# ESP8266_MySensorsGateway_v1_4_1.net
KiCad netlist of a schematic drawn in EAGLE
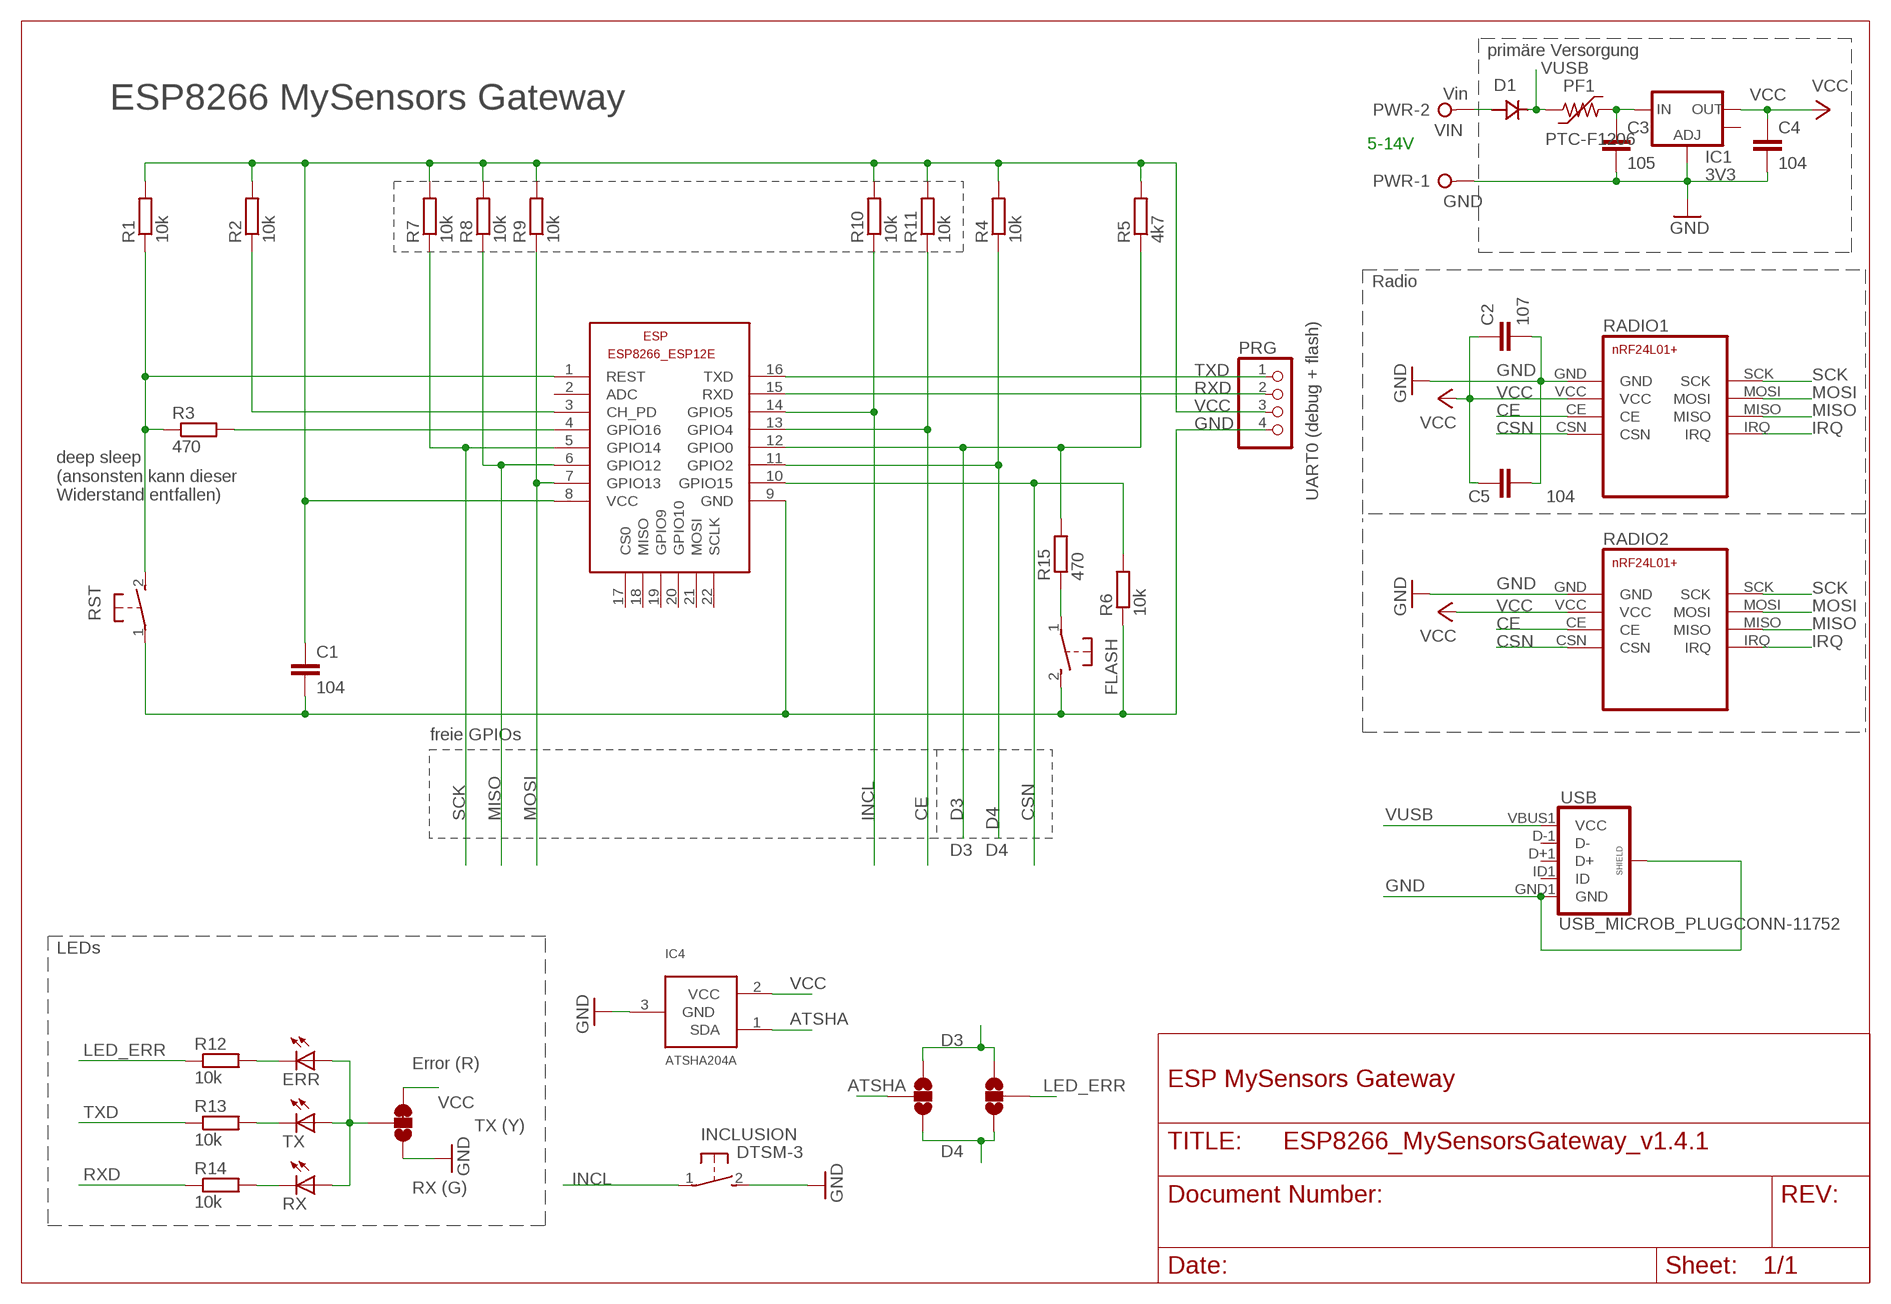
[diagram p0: schematic, sheet 1]

(export (version "E")
  (design (tool "Eeschema 10.0.6"))
  (components
    (comp (ref "C1")
      (value "104")
      (footprint "eagle-import:C0805")
      (libsource (lib "eagle-import") (part "C-EUC0805"))
    )
    (comp (ref "C2")
      (value "107")
      (footprint "eagle-import:MY1210")
      (libsource (lib "eagle-import") (part "C"))
    )
    (comp (ref "C3")
      (value "105")
      (footprint "eagle-import:C0805")
      (libsource (lib "eagle-import") (part "C-EUC0805"))
    )
    (comp (ref "C4")
      (value "104")
      (footprint "eagle-import:C0805")
      (libsource (lib "eagle-import") (part "C-EUC0805"))
    )
    (comp (ref "C5")
      (value "104")
      (footprint "eagle-import:C0805")
      (libsource (lib "eagle-import") (part "C-EUC0805"))
    )
    (comp (ref "D1")
      (value "SS14")
      (footprint "eagle-import:DO214")
      (libsource (lib "eagle-import") (part "SS14"))
    )
    (comp (ref "ERR")
      (value "R")
      (footprint "eagle-import:CHIPLED_1206")
      (libsource (lib "eagle-import") (part "LEDCHIPLED_1206"))
    )
    (comp (ref "ESP")
      (value "µC")
      (footprint "eagle-import:ESP8266-ESP12E")
      (libsource (lib "eagle-import") (part "ESP8266-12EESP8266-ESP12E"))
    )
    (comp (ref "FLASH")
      (value "DTSM-3")
      (footprint "eagle-import:DTSM-3")
      (libsource (lib "eagle-import") (part "DTSM-3"))
    )
    (comp (ref "IC1")
      (value "3V3")
      (footprint "eagle-import:SOT223")
      (libsource (lib "eagle-import") (part "V_REG_LM1117SOT223"))
    )
    (comp (ref "IC4")
      (value "ATSHA204A")
      (footprint "eagle-import:SOT23")
      (libsource (lib "eagle-import") (part "ATSHA204A"))
    )
    (comp (ref "INCLUSION")
      (value "DTSM-3")
      (footprint "eagle-import:DTSM-3")
      (libsource (lib "eagle-import") (part "DTSM-3"))
    )
    (comp (ref "PF1")
      (value "PTC-F1206")
      (footprint "eagle-import:F1206")
      (libsource (lib "eagle-import") (part "PTC-F1206"))
    )
    (comp (ref "PRG")
      (value "PINHD-1X4_S")
      (footprint "eagle-import:1X04")
      (libsource (lib "eagle-import") (part "PINHD-1X4_S"))
    )
    (comp (ref "PWR")
      (value "Vin")
      (footprint "eagle-import:W237-132")
      (libsource (lib "eagle-import") (part "W237-02P"))
    )
    (comp (ref "R1")
      (value "10k")
      (footprint "eagle-import:R0805")
      (libsource (lib "eagle-import") (part "resistor_R-EU_R0805"))
    )
    (comp (ref "R2")
      (value "10k")
      (footprint "eagle-import:R0805")
      (libsource (lib "eagle-import") (part "resistor_R-EU_R0805"))
    )
    (comp (ref "R3")
      (value "470")
      (footprint "eagle-import:R0805")
      (libsource (lib "eagle-import") (part "resistor_R-EU_R0805"))
    )
    (comp (ref "R4")
      (value "10k")
      (footprint "eagle-import:R0805")
      (libsource (lib "eagle-import") (part "resistor_R-EU_R0805"))
    )
    (comp (ref "R5")
      (value "4k7")
      (footprint "eagle-import:R0805")
      (libsource (lib "eagle-import") (part "resistor_R-EU_R0805"))
    )
    (comp (ref "R6")
      (value "10k")
      (footprint "eagle-import:R0805")
      (libsource (lib "eagle-import") (part "resistor_R-EU_R0805"))
    )
    (comp (ref "R7")
      (value "10k")
      (footprint "eagle-import:R0805")
      (libsource (lib "eagle-import") (part "resistor_R-EU_R0805"))
    )
    (comp (ref "R8")
      (value "10k")
      (footprint "eagle-import:R0805")
      (libsource (lib "eagle-import") (part "resistor_R-EU_R0805"))
    )
    (comp (ref "R9")
      (value "10k")
      (footprint "eagle-import:R0805")
      (libsource (lib "eagle-import") (part "resistor_R-EU_R0805"))
    )
    (comp (ref "R10")
      (value "10k")
      (footprint "eagle-import:R0805")
      (libsource (lib "eagle-import") (part "resistor_R-EU_R0805"))
    )
    (comp (ref "R11")
      (value "10k")
      (footprint "eagle-import:R0805")
      (libsource (lib "eagle-import") (part "resistor_R-EU_R0805"))
    )
    (comp (ref "R12")
      (value "10k")
      (footprint "eagle-import:R0805")
      (libsource (lib "eagle-import") (part "R-EU_R0805"))
    )
    (comp (ref "R13")
      (value "10k")
      (footprint "eagle-import:R0805")
      (libsource (lib "eagle-import") (part "R-EU_R0805"))
    )
    (comp (ref "R14")
      (value "10k")
      (footprint "eagle-import:R0805")
      (libsource (lib "eagle-import") (part "R-EU_R0805"))
    )
    (comp (ref "R15")
      (value "470")
      (footprint "eagle-import:R0805")
      (libsource (lib "eagle-import") (part "resistor_R-EU_R0805"))
    )
    (comp (ref "RADIO1")
      (value "NRF24L01+")
      (footprint "eagle-import:NRF24L01+")
      (libsource (lib "eagle-import") (part "NRF24L01+"))
    )
    (comp (ref "RADIO2")
      (value "NRF24L01+NRF24L01+MINI")
      (footprint "eagle-import:NRF24L01+MINI")
      (libsource (lib "eagle-import") (part "NRF24L01+NRF24L01+MINI"))
    )
    (comp (ref "RST")
      (value "DTSM-3")
      (footprint "eagle-import:DTSM-3")
      (libsource (lib "eagle-import") (part "DTSM-3"))
    )
    (comp (ref "RX")
      (value "G")
      (footprint "eagle-import:CHIPLED_1206")
      (libsource (lib "eagle-import") (part "LEDCHIPLED_1206"))
    )
    (comp (ref "SJ1")
      (value "JUMPER-PAD-3-2OF3_NC_BY_TRACE_SMALL")
      (footprint "eagle-import:PAD-JUMPER-3-2OF3_NC_BY_TRACE_YES_SILK_FULL_BOX")
      (libsource (lib "eagle-import") (part "JUMPER-PAD-3-2OF3_NC_BY_TRACE_SMALL"))
    )
    (comp (ref "SJ2")
      (value "JUMPER-PAD-3-NOYES_SILK")
      (footprint "eagle-import:PAD-JUMPER-3-NO_YES_SILK")
      (libsource (lib "eagle-import") (part "JUMPER-PAD-3-NOYES_SILK"))
    )
    (comp (ref "SJ3")
      (value "JUMPER-PAD-3-NOYES_SILK")
      (footprint "eagle-import:PAD-JUMPER-3-NO_YES_SILK")
      (libsource (lib "eagle-import") (part "JUMPER-PAD-3-NOYES_SILK"))
    )
    (comp (ref "TX")
      (value "Y")
      (footprint "eagle-import:CHIPLED_1206")
      (libsource (lib "eagle-import") (part "LEDCHIPLED_1206"))
    )
    (comp (ref "USB")
      (value "USB_MICROB_PLUGCONN-11752")
      (footprint "eagle-import:USB-B-MICRO-SMD_V03")
      (libsource (lib "eagle-import") (part "USB_MICROB_PLUGCONN-11752"))
    )
  )
  (nets
    (net (code "1") (name "/ATSHA") (class "Default")
      (node (ref "IC4") (pin "1") (pinfunction "SDA_1") (pintype "bidirectional"))
      (node (ref "SJ2") (pin "2") (pinfunction "2_2") (pintype "passive"))
    )
    (net (code "2") (name "/CE") (class "Default")
      (node (ref "ESP") (pin "13") (pinfunction "GPIO4_13") (pintype "bidirectional"))
      (node (ref "R11") (pin "1") (pinfunction "1_1") (pintype "passive"))
      (node (ref "RADIO1") (pin "CE") (pinfunction "CE_CE") (pintype "bidirectional"))
      (node (ref "RADIO2") (pin "CE") (pinfunction "CE_CE") (pintype "bidirectional"))
    )
    (net (code "3") (name "/CSN") (class "Default")
      (node (ref "ESP") (pin "10") (pinfunction "GPIO15_10") (pintype "bidirectional"))
      (node (ref "R6") (pin "2") (pinfunction "2_2") (pintype "passive"))
      (node (ref "RADIO1") (pin "CSN") (pinfunction "CSN_CSN") (pintype "bidirectional"))
      (node (ref "RADIO2") (pin "CSN") (pinfunction "CSN_CSN") (pintype "bidirectional"))
    )
    (net (code "4") (name "/D3") (class "Default")
      (node (ref "ESP") (pin "12") (pinfunction "GPIO0_12") (pintype "bidirectional"))
      (node (ref "R15") (pin "2") (pinfunction "2_2") (pintype "passive"))
      (node (ref "R5") (pin "1") (pinfunction "1_1") (pintype "passive"))
      (node (ref "SJ2") (pin "3") (pinfunction "3_3") (pintype "passive"))
      (node (ref "SJ3") (pin "1") (pinfunction "1_1") (pintype "passive"))
    )
    (net (code "5") (name "/D4") (class "Default")
      (node (ref "ESP") (pin "11") (pinfunction "GPIO2_11") (pintype "bidirectional"))
      (node (ref "R4") (pin "1") (pinfunction "1_1") (pintype "passive"))
      (node (ref "SJ2") (pin "1") (pinfunction "1_1") (pintype "passive"))
      (node (ref "SJ3") (pin "3") (pinfunction "3_3") (pintype "passive"))
    )
    (net (code "6") (name "/INCL") (class "Default")
      (node (ref "ESP") (pin "14") (pinfunction "GPIO5_14") (pintype "bidirectional"))
      (node (ref "INCLUSION") (pin "1") (pinfunction "1_1") (pintype "passive"))
      (node (ref "R10") (pin "1") (pinfunction "1_1") (pintype "passive"))
    )
    (net (code "7") (name "/IRQ") (class "Default")
      (node (ref "RADIO1") (pin "IRQ") (pinfunction "IRQ_IRQ") (pintype "bidirectional"))
      (node (ref "RADIO2") (pin "IRQ") (pinfunction "IRQ_IRQ") (pintype "bidirectional"))
    )
    (net (code "8") (name "/LED_ERR") (class "Default")
      (node (ref "R12") (pin "1") (pinfunction "1_1") (pintype "passive"))
      (node (ref "SJ3") (pin "2") (pinfunction "2_2") (pintype "passive"))
    )
    (net (code "9") (name "/MISO") (class "Default")
      (node (ref "ESP") (pin "6") (pinfunction "GPIO12_6") (pintype "bidirectional"))
      (node (ref "R8") (pin "1") (pinfunction "1_1") (pintype "passive"))
      (node (ref "RADIO1") (pin "MISO") (pinfunction "MISO_MISO") (pintype "bidirectional"))
      (node (ref "RADIO2") (pin "MISO") (pinfunction "MISO_MISO") (pintype "bidirectional"))
    )
    (net (code "10") (name "/MOSI") (class "Default")
      (node (ref "ESP") (pin "7") (pinfunction "GPIO13_7") (pintype "bidirectional"))
      (node (ref "R9") (pin "1") (pinfunction "1_1") (pintype "passive"))
      (node (ref "RADIO1") (pin "MOSI") (pinfunction "MOSI_MOSI") (pintype "bidirectional"))
      (node (ref "RADIO2") (pin "MOSI") (pinfunction "MOSI_MOSI") (pintype "bidirectional"))
    )
    (net (code "11") (name "/RXD") (class "Default")
      (node (ref "ESP") (pin "15") (pinfunction "RXD_15") (pintype "bidirectional"))
      (node (ref "PRG") (pin "2") (pinfunction "2_2") (pintype "passive"))
      (node (ref "R14") (pin "1") (pinfunction "1_1") (pintype "passive"))
    )
    (net (code "12") (name "/SCK") (class "Default")
      (node (ref "ESP") (pin "5") (pinfunction "GPIO14_5") (pintype "bidirectional"))
      (node (ref "R7") (pin "1") (pinfunction "1_1") (pintype "passive"))
      (node (ref "RADIO1") (pin "SCK") (pinfunction "SCK_SCK") (pintype "bidirectional"))
      (node (ref "RADIO2") (pin "SCK") (pinfunction "SCK_SCK") (pintype "bidirectional"))
    )
    (net (code "13") (name "/TXD") (class "Default")
      (node (ref "ESP") (pin "16") (pinfunction "TXD_16") (pintype "bidirectional"))
      (node (ref "PRG") (pin "1") (pinfunction "1_1") (pintype "passive"))
      (node (ref "R13") (pin "1") (pinfunction "1_1") (pintype "passive"))
    )
    (net (code "14") (name "/VIN") (class "Default")
      (node (ref "D1") (pin "ANODE") (pinfunction "ANODE_ANODE") (pintype "bidirectional"))
      (node (ref "PWR") (pin "2") (pinfunction "KL_2") (pintype "passive"))
    )
    (net (code "15") (name "/VUSB") (class "Default")
      (node (ref "D1") (pin "CATHODE") (pinfunction "CATHODE_CATHODE") (pintype "bidirectional"))
      (node (ref "PF1") (pin "1") (pinfunction "1_1") (pintype "passive"))
      (node (ref "USB") (pin "VBUS1") (pinfunction "VCC_VBUS1") (pintype "bidirectional"))
    )
    (net (code "16") (name "GND") (class "Default")
      (node (ref "C1") (pin "2") (pinfunction "2_2") (pintype "passive"))
      (node (ref "C2") (pin "2") (pinfunction "2_2") (pintype "passive"))
      (node (ref "C3") (pin "2") (pinfunction "2_2") (pintype "passive"))
      (node (ref "C4") (pin "2") (pinfunction "2_2") (pintype "passive"))
      (node (ref "C5") (pin "2") (pinfunction "2_2") (pintype "passive"))
      (node (ref "ESP") (pin "9") (pinfunction "GND_9") (pintype "bidirectional"))
      (node (ref "FLASH") (pin "2") (pinfunction "2_2") (pintype "passive"))
      (node (ref "IC1") (pin "1") (pinfunction "ADJ_1") (pintype "input"))
      (node (ref "IC4") (pin "3") (pinfunction "GND_3") (pintype "bidirectional"))
      (node (ref "INCLUSION") (pin "2") (pinfunction "2_2") (pintype "passive"))
      (node (ref "PRG") (pin "4") (pinfunction "4_4") (pintype "passive"))
      (node (ref "PWR") (pin "1") (pinfunction "KL_1") (pintype "passive"))
      (node (ref "R6") (pin "1") (pinfunction "1_1") (pintype "passive"))
      (node (ref "RADIO1") (pin "GND") (pinfunction "GND_GND") (pintype "power_in"))
      (node (ref "RADIO2") (pin "GND") (pinfunction "GND_GND") (pintype "power_in"))
      (node (ref "RST") (pin "1") (pinfunction "1_1") (pintype "passive"))
      (node (ref "SJ1") (pin "1") (pinfunction "1_1") (pintype "passive"))
      (node (ref "USB") (pin "GND1") (pinfunction "GND_GND1") (pintype "bidirectional"))
      (node (ref "USB") (pin "SHIELD1") (pinfunction "SHIELD_SHIELD1") (pintype "bidirectional"))
      (node (ref "USB") (pin "SHIELD2") (pinfunction "SHIELD_SHIELD2") (pintype "bidirectional"))
      (node (ref "USB") (pin "SHIELD3") (pinfunction "SHIELD_SHIELD3") (pintype "bidirectional"))
    )
    (net (code "17") (name "Net-(ERR-PadA)") (class "Default")
      (node (ref "ERR") (pin "A") (pinfunction "A_A") (pintype "passive"))
      (node (ref "RX") (pin "A") (pinfunction "A_A") (pintype "passive"))
      (node (ref "SJ1") (pin "2") (pinfunction "2_2") (pintype "passive"))
      (node (ref "TX") (pin "A") (pinfunction "A_A") (pintype "passive"))
    )
    (net (code "18") (name "Net-(ERR-PadC)") (class "Default")
      (node (ref "ERR") (pin "C") (pinfunction "C_C") (pintype "passive"))
      (node (ref "R12") (pin "2") (pinfunction "2_2") (pintype "passive"))
    )
    (net (code "19") (name "Net-(ESP-CH_PD)") (class "Default")
      (node (ref "ESP") (pin "3") (pinfunction "CH_PD_3") (pintype "bidirectional"))
      (node (ref "R2") (pin "1") (pinfunction "1_1") (pintype "passive"))
    )
    (net (code "20") (name "Net-(ESP-GPIO16)") (class "Default")
      (node (ref "ESP") (pin "4") (pinfunction "GPIO16_4") (pintype "bidirectional"))
      (node (ref "R3") (pin "2") (pinfunction "2_2") (pintype "passive"))
    )
    (net (code "21") (name "Net-(ESP-REST)") (class "Default")
      (node (ref "ESP") (pin "1") (pinfunction "REST_1") (pintype "bidirectional"))
      (node (ref "R1") (pin "1") (pinfunction "1_1") (pintype "passive"))
      (node (ref "R3") (pin "1") (pinfunction "1_1") (pintype "passive"))
      (node (ref "RST") (pin "2") (pinfunction "2_2") (pintype "passive"))
    )
    (net (code "22") (name "Net-(FLASH-Pad1)") (class "Default")
      (node (ref "FLASH") (pin "1") (pinfunction "1_1") (pintype "passive"))
      (node (ref "R15") (pin "1") (pinfunction "1_1") (pintype "passive"))
    )
    (net (code "23") (name "Net-(IC1-IN)") (class "Default")
      (node (ref "C3") (pin "1") (pinfunction "1_1") (pintype "passive"))
      (node (ref "IC1") (pin "3") (pinfunction "IN_3") (pintype "input"))
      (node (ref "PF1") (pin "2") (pinfunction "2_2") (pintype "passive"))
    )
    (net (code "24") (name "Net-(R13-Pad2)") (class "Default")
      (node (ref "R13") (pin "2") (pinfunction "2_2") (pintype "passive"))
      (node (ref "TX") (pin "C") (pinfunction "C_C") (pintype "passive"))
    )
    (net (code "25") (name "Net-(R14-Pad2)") (class "Default")
      (node (ref "R14") (pin "2") (pinfunction "2_2") (pintype "passive"))
      (node (ref "RX") (pin "C") (pinfunction "C_C") (pintype "passive"))
    )
    (net (code "26") (name "VCC") (class "Default")
      (node (ref "C1") (pin "1") (pinfunction "1_1") (pintype "passive"))
      (node (ref "C2") (pin "1") (pinfunction "1_1") (pintype "passive"))
      (node (ref "C4") (pin "1") (pinfunction "1_1") (pintype "passive"))
      (node (ref "C5") (pin "1") (pinfunction "1_1") (pintype "passive"))
      (node (ref "ESP") (pin "8") (pinfunction "VCC_8") (pintype "bidirectional"))
      (node (ref "IC1") (pin "2") (pinfunction "OUT_2") (pintype "output"))
      (node (ref "IC4") (pin "2") (pinfunction "VCC_2") (pintype "bidirectional"))
      (node (ref "PRG") (pin "3") (pinfunction "3_3") (pintype "passive"))
      (node (ref "R1") (pin "2") (pinfunction "2_2") (pintype "passive"))
      (node (ref "R10") (pin "2") (pinfunction "2_2") (pintype "passive"))
      (node (ref "R11") (pin "2") (pinfunction "2_2") (pintype "passive"))
      (node (ref "R2") (pin "2") (pinfunction "2_2") (pintype "passive"))
      (node (ref "R4") (pin "2") (pinfunction "2_2") (pintype "passive"))
      (node (ref "R5") (pin "2") (pinfunction "2_2") (pintype "passive"))
      (node (ref "R7") (pin "2") (pinfunction "2_2") (pintype "passive"))
      (node (ref "R8") (pin "2") (pinfunction "2_2") (pintype "passive"))
      (node (ref "R9") (pin "2") (pinfunction "2_2") (pintype "passive"))
      (node (ref "RADIO1") (pin "VCC") (pinfunction "VCC_VCC") (pintype "power_in"))
      (node (ref "RADIO2") (pin "VCC") (pinfunction "VCC_VCC") (pintype "power_in"))
      (node (ref "SJ1") (pin "3") (pinfunction "3_3") (pintype "passive"))
    )
    (net (code "27") (name "unconnected-(ESP-ADC-Pad2)") (class "Default")
      (node (ref "ESP") (pin "2") (pinfunction "ADC_2") (pintype "bidirectional"))
    )
    (net (code "28") (name "unconnected-(ESP-CS0-Pad17)") (class "Default")
      (node (ref "ESP") (pin "17") (pinfunction "CS0_17") (pintype "bidirectional"))
    )
    (net (code "29") (name "unconnected-(ESP-GPIO9-Pad19)") (class "Default")
      (node (ref "ESP") (pin "19") (pinfunction "GPIO9_19") (pintype "bidirectional"))
    )
    (net (code "30") (name "unconnected-(ESP-GPIO10-Pad20)") (class "Default")
      (node (ref "ESP") (pin "20") (pinfunction "GPIO10_20") (pintype "bidirectional"))
    )
    (net (code "31") (name "unconnected-(ESP-MISO-Pad18)") (class "Default")
      (node (ref "ESP") (pin "18") (pinfunction "MISO_18") (pintype "bidirectional"))
    )
    (net (code "32") (name "unconnected-(ESP-MOSI-Pad21)") (class "Default")
      (node (ref "ESP") (pin "21") (pinfunction "MOSI_21") (pintype "bidirectional"))
    )
    (net (code "33") (name "unconnected-(ESP-SCLK-Pad22)") (class "Default")
      (node (ref "ESP") (pin "22") (pinfunction "SCLK_22") (pintype "bidirectional"))
    )
    (net (code "34") (name "unconnected-(IC1-OUT-Pad4)") (class "Default")
      (node (ref "IC1") (pin "4") (pinfunction "OUT_4") (pintype "output"))
    )
    (net (code "35") (name "unconnected-(USB-D+-PadD+1)") (class "Default")
      (node (ref "USB") (pin "D+1") (pinfunction "D+_D+1") (pintype "bidirectional"))
    )
    (net (code "36") (name "unconnected-(USB-D--PadD-1)") (class "Default")
      (node (ref "USB") (pin "D-1") (pinfunction "D-_D-1") (pintype "bidirectional"))
    )
    (net (code "37") (name "unconnected-(USB-ID-PadID1)") (class "Default")
      (node (ref "USB") (pin "ID1") (pinfunction "ID_ID1") (pintype "bidirectional"))
    )
  )
)
